# 6301_Lab3_PTAT.net
KiCad netlist of a schematic drawn in Altium Designer
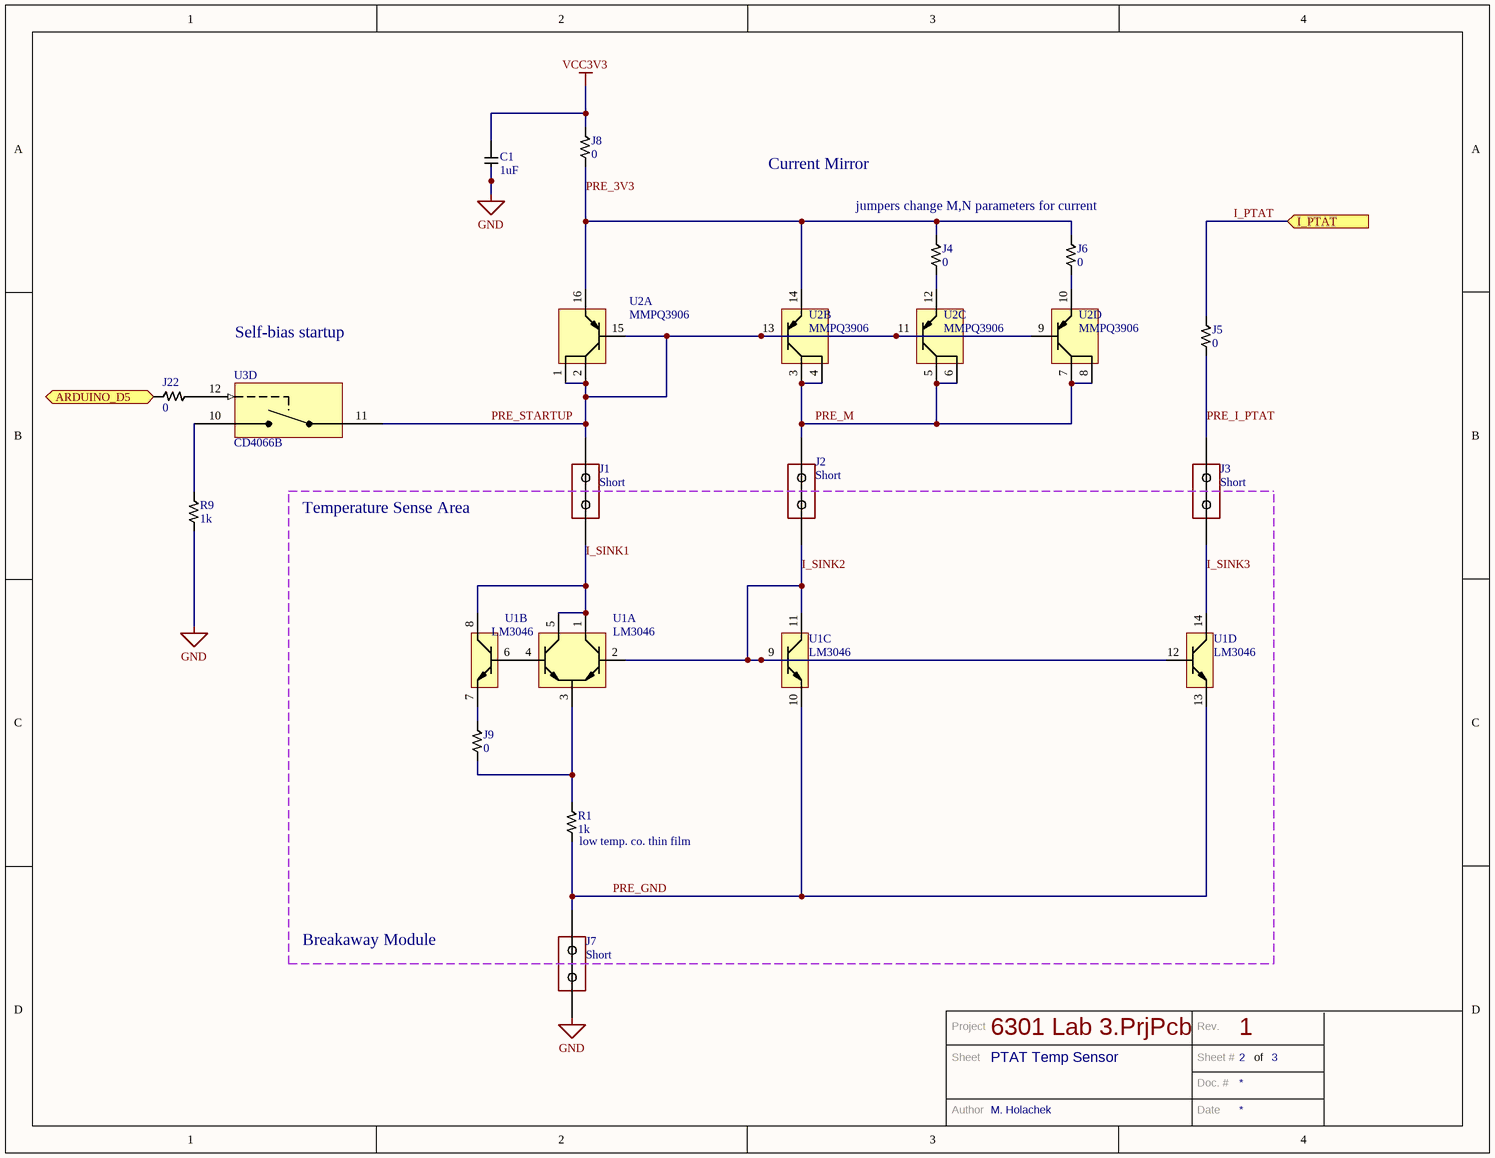
[diagram p0: 6301 Lab3 PTAT.SchDoc]

(export (version "E")
  (design (tool "Eeschema 10.0.6"))
  (components
    (comp (ref "C1")
      (value "1uF")
      (footprint "CAP0805")
      (description "Capacitor, 0805 Package")
      (fields (field (name "TOLERANCE") "10%") (field (name "VOLTAGE") "25V"))
      (libsource (lib "6301 Lab 3") (part "Capacitor"))
    )
    (comp (ref "J1")
      (value "Short")
      (footprint "1X02_SHORT")
      (description "Shorted TH pins in wide configuration")
      (libsource (lib "6301 Lab 3") (part "1x2 Wide Short"))
    )
    (comp (ref "J2")
      (value "Short")
      (footprint "1X02_SHORT")
      (description "Shorted TH pins in wide configuration")
      (libsource (lib "") (part "1x2 Wide Short_1"))
    )
    (comp (ref "J3")
      (value "Short")
      (footprint "1X02_SHORT")
      (description "Shorted TH pins in wide configuration")
      (libsource (lib "6301 Lab 3") (part "1x2 Wide Short"))
    )
    (comp (ref "J4")
      (value "0")
      (footprint "JUMP0402")
      (description "Jumper, 0402 Package")
      (libsource (lib "6301 Lab 3") (part "Jumper 0402"))
    )
    (comp (ref "J5")
      (value "0")
      (footprint "JUMP0402")
      (description "Jumper, 0402 Package")
      (libsource (lib "6301 Lab 3") (part "Jumper 0402"))
    )
    (comp (ref "J6")
      (value "0")
      (footprint "JUMP0402")
      (description "Jumper, 0402 Package")
      (libsource (lib "6301 Lab 3") (part "Jumper 0402"))
    )
    (comp (ref "J7")
      (value "Short")
      (footprint "1X02_SHORT")
      (description "Shorted TH pins in wide configuration")
      (libsource (lib "6301 Lab 3") (part "1x2 Wide Short"))
    )
    (comp (ref "J8")
      (value "0")
      (footprint "JUMP0402")
      (description "Jumper, 0402 Package")
      (libsource (lib "6301 Lab 3") (part "Jumper 0402"))
    )
    (comp (ref "J9")
      (value "0")
      (footprint "JUMP0402")
      (description "Jumper, 0402 Package")
      (libsource (lib "6301 Lab 3") (part "Jumper 0402"))
    )
    (comp (ref "J22")
      (value "0")
      (footprint "JUMP0402")
      (description "Jumper, 0402 Package")
      (libsource (lib "6301 Lab 3") (part "Jumper 0402"))
    )
    (comp (ref "R1")
      (value "1k")
      (footprint "RES0805")
      (description "Resistor, 0805 Package")
      (fields (field (name "TOLERANCE") "0.1%"))
      (libsource (lib "6301 Lab 3") (part "Resistor"))
    )
    (comp (ref "R9")
      (value "1k")
      (footprint "RES0805")
      (description "Resistor, 0805 Package")
      (fields (field (name "TOLERANCE") "1%"))
      (libsource (lib "6301 Lab 3") (part "Resistor"))
    )
    (comp (ref "U1")
      (value "LM3046")
      (footprint "SOIC14")
      (description "NPN Silicon Quad Transistor Array")
      (libsource (lib "6301 Lab 3") (part "LM3046"))
    )
    (comp (ref "U2")
      (value "MMPQ3906")
      (footprint "SOIC16")
      (description "PNP Silicon Quad Transistor Array")
      (libsource (lib "6301 Lab 3") (part "MMPQ3906"))
    )
    (comp (ref "U3")
      (value "CD4066B")
      (footprint "SOIC14")
      (description "CMOS Quad Bilateral Switch")
      (fields (field (name "MANUFACTURER") "Texas Instruments"))
      (libsource (lib "6301 Lab 3") (part "CD4066B"))
    )
  )
  (nets
    (net (code "1") (name "/ARDUINO_D5") (class "Default")
      (node (ref "J22") (pin "1") (pinfunction "1_1") (pintype "passive"))
    )
    (net (code "2") (name "/I_PTAT") (class "Default")
      (node (ref "J5") (pin "2") (pinfunction "2_2") (pintype "passive"))
    )
    (net (code "3") (name "/I_SINK1") (class "Default")
      (node (ref "J1") (pin "1") (pinfunction "1_1") (pintype "passive"))
      (node (ref "U1") (pin "1") (pinfunction "Q1AC_1") (pintype "passive"))
      (node (ref "U1") (pin "5") (pinfunction "Q1BC_5") (pintype "passive"))
      (node (ref "U1") (pin "8") (pinfunction "Q2C_8") (pintype "passive"))
    )
    (net (code "4") (name "/I_SINK2") (class "Default")
      (node (ref "J2") (pin "2") (pinfunction "2_2") (pintype "passive"))
      (node (ref "U1") (pin "11") (pinfunction "Q3C_11") (pintype "passive"))
      (node (ref "U1") (pin "12") (pinfunction "Q4B_12") (pintype "passive"))
      (node (ref "U1") (pin "2") (pinfunction "Q1AB_2") (pintype "passive"))
      (node (ref "U1") (pin "9") (pinfunction "Q3B_9") (pintype "passive"))
    )
    (net (code "5") (name "/I_SINK3") (class "Default")
      (node (ref "J3") (pin "1") (pinfunction "1_1") (pintype "passive"))
      (node (ref "U1") (pin "14") (pinfunction "Q4C_14") (pintype "passive"))
    )
    (net (code "6") (name "/PRE_3V3") (class "Default")
      (node (ref "J4") (pin "2") (pinfunction "2_2") (pintype "passive"))
      (node (ref "J6") (pin "2") (pinfunction "2_2") (pintype "passive"))
      (node (ref "J8") (pin "1") (pinfunction "1_1") (pintype "passive"))
      (node (ref "U2") (pin "14") (pinfunction "Q2E_14") (pintype "passive"))
      (node (ref "U2") (pin "16") (pinfunction "Q1E_16") (pintype "passive"))
    )
    (net (code "7") (name "/PRE_GND") (class "Default")
      (node (ref "J7") (pin "2") (pinfunction "2_2") (pintype "passive"))
      (node (ref "R1") (pin "1") (pinfunction "1_1") (pintype "passive"))
      (node (ref "U1") (pin "10") (pinfunction "Q3E_10") (pintype "passive"))
      (node (ref "U1") (pin "13") (pinfunction "Q4E_13") (pintype "passive"))
    )
    (net (code "8") (name "/PRE_I_PTAT") (class "Default")
      (node (ref "J3") (pin "2") (pinfunction "2_2") (pintype "passive"))
      (node (ref "J5") (pin "1") (pinfunction "1_1") (pintype "passive"))
    )
    (net (code "9") (name "/PRE_M") (class "Default")
      (node (ref "J2") (pin "1") (pinfunction "1_1") (pintype "passive"))
      (node (ref "U2") (pin "3") (pinfunction "Q2C_3") (pintype "passive"))
      (node (ref "U2") (pin "4") (pinfunction "Q1C_4") (pintype "passive"))
      (node (ref "U2") (pin "5") (pinfunction "Q3C_5") (pintype "passive"))
      (node (ref "U2") (pin "6") (pinfunction "Q1C_6") (pintype "passive"))
      (node (ref "U2") (pin "7") (pinfunction "Q4C_7") (pintype "passive"))
      (node (ref "U2") (pin "8") (pinfunction "Q1C_8") (pintype "passive"))
    )
    (net (code "10") (name "/PRE_STARTUP") (class "Default")
      (node (ref "J1") (pin "2") (pinfunction "2_2") (pintype "passive"))
      (node (ref "U2") (pin "1") (pinfunction "Q1C_1") (pintype "passive"))
      (node (ref "U2") (pin "11") (pinfunction "Q3B_11") (pintype "passive"))
      (node (ref "U2") (pin "13") (pinfunction "Q2B_13") (pintype "passive"))
      (node (ref "U2") (pin "15") (pinfunction "Q1B_15") (pintype "passive"))
      (node (ref "U2") (pin "2") (pinfunction "Q1C_2") (pintype "passive"))
      (node (ref "U2") (pin "9") (pinfunction "Q4B_9") (pintype "passive"))
      (node (ref "U3") (pin "11") (pinfunction "IN_D_11") (pintype "passive"))
    )
    (net (code "11") (name "GND") (class "Default")
      (node (ref "C1") (pin "1") (pinfunction "1_1") (pintype "passive"))
      (node (ref "J7") (pin "1") (pinfunction "1_1") (pintype "passive"))
      (node (ref "R9") (pin "1") (pinfunction "1_1") (pintype "passive"))
    )
    (net (code "12") (name "Net-(U1A-Q1BB)") (class "Default")
      (node (ref "U1") (pin "4") (pinfunction "Q1BB_4") (pintype "passive"))
      (node (ref "U1") (pin "6") (pinfunction "Q2B_6") (pintype "passive"))
    )
    (net (code "13") (name "Net-(U1A-Q1E)") (class "Default")
      (node (ref "J9") (pin "1") (pinfunction "1_1") (pintype "passive"))
      (node (ref "R1") (pin "2") (pinfunction "2_2") (pintype "passive"))
      (node (ref "U1") (pin "3") (pinfunction "Q1E_3") (pintype "passive"))
    )
    (net (code "14") (name "Net-(U1B-Q2E)") (class "Default")
      (node (ref "J9") (pin "2") (pinfunction "2_2") (pintype "passive"))
      (node (ref "U1") (pin "7") (pinfunction "Q2E_7") (pintype "passive"))
    )
    (net (code "15") (name "Net-(U2C-Q3E)") (class "Default")
      (node (ref "J4") (pin "1") (pinfunction "1_1") (pintype "passive"))
      (node (ref "U2") (pin "12") (pinfunction "Q3E_12") (pintype "passive"))
    )
    (net (code "16") (name "Net-(U2D-Q4E)") (class "Default")
      (node (ref "J6") (pin "1") (pinfunction "1_1") (pintype "passive"))
      (node (ref "U2") (pin "10") (pinfunction "Q4E_10") (pintype "passive"))
    )
    (net (code "17") (name "Net-(U3D-EN_D)") (class "Default")
      (node (ref "J22") (pin "2") (pinfunction "2_2") (pintype "passive"))
      (node (ref "U3") (pin "12") (pinfunction "EN_D_12") (pintype "input"))
    )
    (net (code "18") (name "Net-(U3D-OUT_D)") (class "Default")
      (node (ref "R9") (pin "2") (pinfunction "2_2") (pintype "passive"))
      (node (ref "U3") (pin "10") (pinfunction "OUT_D_10") (pintype "passive"))
    )
    (net (code "19") (name "VCC3V3") (class "Default")
      (node (ref "C1") (pin "2") (pinfunction "2_2") (pintype "passive"))
      (node (ref "J8") (pin "2") (pinfunction "2_2") (pintype "passive"))
    )
  )
)
